# chart2.net
KiCad netlist of a schematic drawn in EAGLE
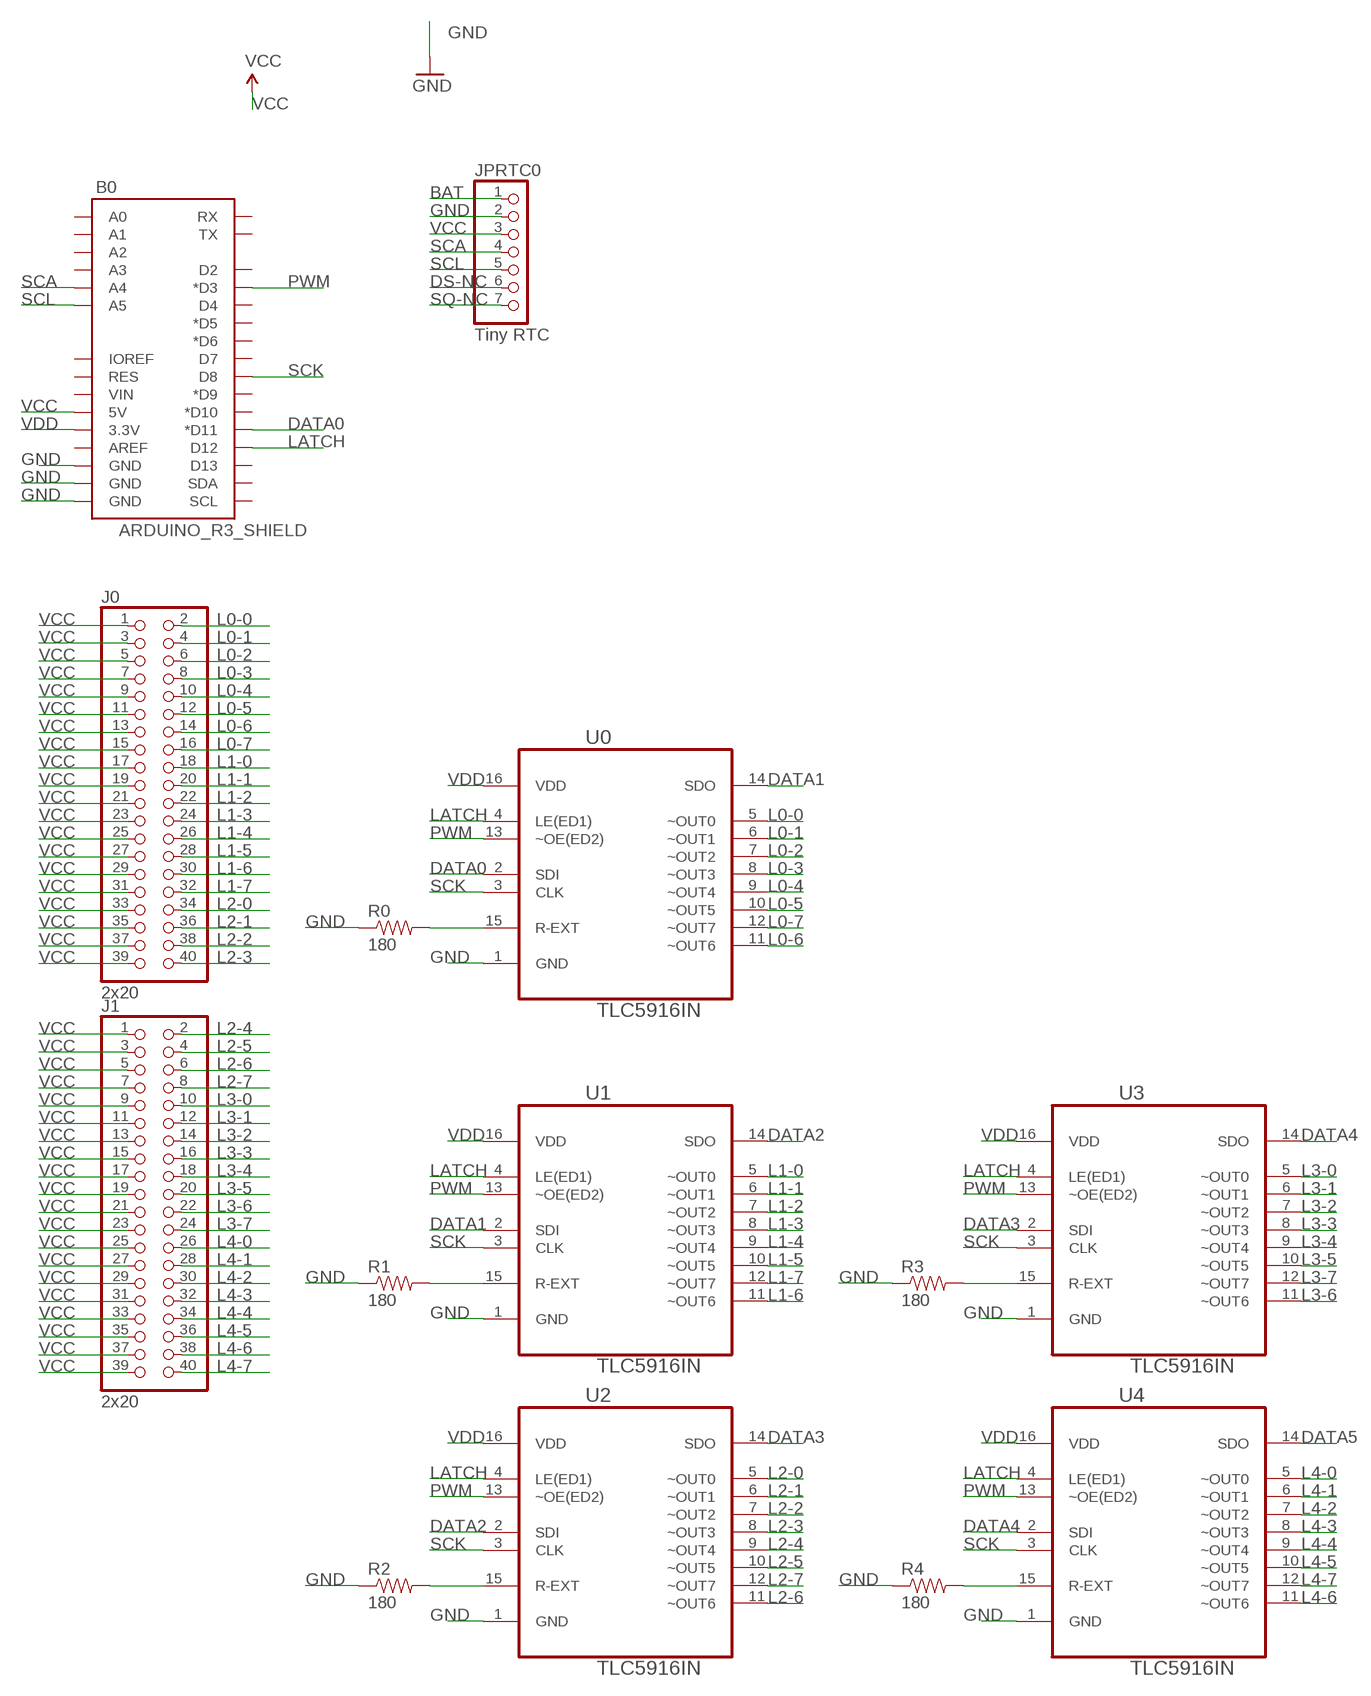
[diagram p0: schematic, sheet 1]

(export (version "E")
  (design (tool "Eeschema 10.0.6"))
  (components
    (comp (ref "B0")
      (value "ARDUINO_R3_SHIELD")
      (footprint "eagle-import:UNO_R3_SHIELD")
      (libsource (lib "eagle-import") (part "ARDUINO_R3_SHIELD"))
    )
    (comp (ref "J0")
      (value "2x20")
      (footprint "eagle-import:2X20_90")
      (libsource (lib "eagle-import") (part "PINHD-2X20/90"))
    )
    (comp (ref "J1")
      (value "2x20")
      (footprint "eagle-import:2X20_90")
      (libsource (lib "eagle-import") (part "PINHD-2X20/90"))
    )
    (comp (ref "JPRTC0")
      (value "Tiny RTC")
      (footprint "eagle-import:1X07")
      (libsource (lib "eagle-import") (part "PINHD-1X7"))
    )
    (comp (ref "R0")
      (value "180")
      (footprint "eagle-import:AXIAL-0.4")
      (libsource (lib "eagle-import") (part "RESISTORPTH-1/4W"))
    )
    (comp (ref "R1")
      (value "180")
      (footprint "eagle-import:AXIAL-0.4")
      (libsource (lib "eagle-import") (part "RESISTORPTH-1/4W"))
    )
    (comp (ref "R2")
      (value "180")
      (footprint "eagle-import:AXIAL-0.4")
      (libsource (lib "eagle-import") (part "RESISTORPTH-1/4W"))
    )
    (comp (ref "R3")
      (value "180")
      (footprint "eagle-import:AXIAL-0.4")
      (libsource (lib "eagle-import") (part "RESISTORPTH-1/4W"))
    )
    (comp (ref "R4")
      (value "180")
      (footprint "eagle-import:AXIAL-0.4")
      (libsource (lib "eagle-import") (part "RESISTORPTH-1/4W"))
    )
    (comp (ref "U0")
      (value "TLC5916IN")
      (footprint "eagle-import:DIP254P762X508-16")
      (libsource (lib "eagle-import") (part "TLC5916IN"))
    )
    (comp (ref "U1")
      (value "TLC5916IN")
      (footprint "eagle-import:DIP254P762X508-16")
      (libsource (lib "eagle-import") (part "TLC5916IN"))
    )
    (comp (ref "U2")
      (value "TLC5916IN")
      (footprint "eagle-import:DIP254P762X508-16")
      (libsource (lib "eagle-import") (part "TLC5916IN"))
    )
    (comp (ref "U3")
      (value "TLC5916IN")
      (footprint "eagle-import:DIP254P762X508-16")
      (libsource (lib "eagle-import") (part "TLC5916IN"))
    )
    (comp (ref "U4")
      (value "TLC5916IN")
      (footprint "eagle-import:DIP254P762X508-16")
      (libsource (lib "eagle-import") (part "TLC5916IN"))
    )
  )
  (nets
    (net (code "1") (name "/BAT") (class "Default")
      (node (ref "JPRTC0") (pin "1") (pinfunction "1_1") (pintype "passive"))
    )
    (net (code "2") (name "/DATA0") (class "Default")
      (node (ref "B0") (pin "D11") (pinfunction "*D11_D11") (pintype "bidirectional"))
      (node (ref "U0") (pin "2") (pinfunction "SDI_2") (pintype "input"))
    )
    (net (code "3") (name "/DATA1") (class "Default")
      (node (ref "U0") (pin "14") (pinfunction "SDO_14") (pintype "output"))
      (node (ref "U1") (pin "2") (pinfunction "SDI_2") (pintype "input"))
    )
    (net (code "4") (name "/DATA2") (class "Default")
      (node (ref "U1") (pin "14") (pinfunction "SDO_14") (pintype "output"))
      (node (ref "U2") (pin "2") (pinfunction "SDI_2") (pintype "input"))
    )
    (net (code "5") (name "/DATA3") (class "Default")
      (node (ref "U2") (pin "14") (pinfunction "SDO_14") (pintype "output"))
      (node (ref "U3") (pin "2") (pinfunction "SDI_2") (pintype "input"))
    )
    (net (code "6") (name "/DATA4") (class "Default")
      (node (ref "U3") (pin "14") (pinfunction "SDO_14") (pintype "output"))
      (node (ref "U4") (pin "2") (pinfunction "SDI_2") (pintype "input"))
    )
    (net (code "7") (name "/DATA5") (class "Default")
      (node (ref "U4") (pin "14") (pinfunction "SDO_14") (pintype "output"))
    )
    (net (code "8") (name "/DS-NC") (class "Default")
      (node (ref "JPRTC0") (pin "6") (pinfunction "6_6") (pintype "passive"))
    )
    (net (code "9") (name "/L0-0") (class "Default")
      (node (ref "J0") (pin "2") (pinfunction "2_2") (pintype "passive"))
      (node (ref "U0") (pin "5") (pinfunction "~{OUT0}_5") (pintype "output"))
    )
    (net (code "10") (name "/L0-1") (class "Default")
      (node (ref "J0") (pin "4") (pinfunction "4_4") (pintype "passive"))
      (node (ref "U0") (pin "6") (pinfunction "~{OUT1}_6") (pintype "output"))
    )
    (net (code "11") (name "/L0-2") (class "Default")
      (node (ref "J0") (pin "6") (pinfunction "6_6") (pintype "passive"))
      (node (ref "U0") (pin "7") (pinfunction "~{OUT2}_7") (pintype "output"))
    )
    (net (code "12") (name "/L0-3") (class "Default")
      (node (ref "J0") (pin "8") (pinfunction "8_8") (pintype "passive"))
      (node (ref "U0") (pin "8") (pinfunction "~{OUT3}_8") (pintype "output"))
    )
    (net (code "13") (name "/L0-4") (class "Default")
      (node (ref "J0") (pin "10") (pinfunction "10_10") (pintype "passive"))
      (node (ref "U0") (pin "9") (pinfunction "~{OUT4}_9") (pintype "output"))
    )
    (net (code "14") (name "/L0-5") (class "Default")
      (node (ref "J0") (pin "12") (pinfunction "12_12") (pintype "passive"))
      (node (ref "U0") (pin "10") (pinfunction "~{OUT5}_10") (pintype "output"))
    )
    (net (code "15") (name "/L0-6") (class "Default")
      (node (ref "J0") (pin "14") (pinfunction "14_14") (pintype "passive"))
      (node (ref "U0") (pin "11") (pinfunction "~{OUT6}_11") (pintype "output"))
    )
    (net (code "16") (name "/L0-7") (class "Default")
      (node (ref "J0") (pin "16") (pinfunction "16_16") (pintype "passive"))
      (node (ref "U0") (pin "12") (pinfunction "~{OUT7}_12") (pintype "output"))
    )
    (net (code "17") (name "/L1-0") (class "Default")
      (node (ref "J0") (pin "18") (pinfunction "18_18") (pintype "passive"))
      (node (ref "U1") (pin "5") (pinfunction "~{OUT0}_5") (pintype "output"))
    )
    (net (code "18") (name "/L1-1") (class "Default")
      (node (ref "J0") (pin "20") (pinfunction "20_20") (pintype "passive"))
      (node (ref "U1") (pin "6") (pinfunction "~{OUT1}_6") (pintype "output"))
    )
    (net (code "19") (name "/L1-2") (class "Default")
      (node (ref "J0") (pin "22") (pinfunction "22_22") (pintype "passive"))
      (node (ref "U1") (pin "7") (pinfunction "~{OUT2}_7") (pintype "output"))
    )
    (net (code "20") (name "/L1-3") (class "Default")
      (node (ref "J0") (pin "24") (pinfunction "24_24") (pintype "passive"))
      (node (ref "U1") (pin "8") (pinfunction "~{OUT3}_8") (pintype "output"))
    )
    (net (code "21") (name "/L1-4") (class "Default")
      (node (ref "J0") (pin "26") (pinfunction "26_26") (pintype "passive"))
      (node (ref "U1") (pin "9") (pinfunction "~{OUT4}_9") (pintype "output"))
    )
    (net (code "22") (name "/L1-5") (class "Default")
      (node (ref "J0") (pin "28") (pinfunction "28_28") (pintype "passive"))
      (node (ref "U1") (pin "10") (pinfunction "~{OUT5}_10") (pintype "output"))
    )
    (net (code "23") (name "/L1-6") (class "Default")
      (node (ref "J0") (pin "30") (pinfunction "30_30") (pintype "passive"))
      (node (ref "U1") (pin "11") (pinfunction "~{OUT6}_11") (pintype "output"))
    )
    (net (code "24") (name "/L1-7") (class "Default")
      (node (ref "J0") (pin "32") (pinfunction "32_32") (pintype "passive"))
      (node (ref "U1") (pin "12") (pinfunction "~{OUT7}_12") (pintype "output"))
    )
    (net (code "25") (name "/L2-0") (class "Default")
      (node (ref "J0") (pin "34") (pinfunction "34_34") (pintype "passive"))
      (node (ref "U2") (pin "5") (pinfunction "~{OUT0}_5") (pintype "output"))
    )
    (net (code "26") (name "/L2-1") (class "Default")
      (node (ref "J0") (pin "36") (pinfunction "36_36") (pintype "passive"))
      (node (ref "U2") (pin "6") (pinfunction "~{OUT1}_6") (pintype "output"))
    )
    (net (code "27") (name "/L2-2") (class "Default")
      (node (ref "J0") (pin "38") (pinfunction "38_38") (pintype "passive"))
      (node (ref "U2") (pin "7") (pinfunction "~{OUT2}_7") (pintype "output"))
    )
    (net (code "28") (name "/L2-3") (class "Default")
      (node (ref "J0") (pin "40") (pinfunction "40_40") (pintype "passive"))
      (node (ref "U2") (pin "8") (pinfunction "~{OUT3}_8") (pintype "output"))
    )
    (net (code "29") (name "/L2-4") (class "Default")
      (node (ref "J1") (pin "2") (pinfunction "2_2") (pintype "passive"))
      (node (ref "U2") (pin "9") (pinfunction "~{OUT4}_9") (pintype "output"))
    )
    (net (code "30") (name "/L2-5") (class "Default")
      (node (ref "J1") (pin "4") (pinfunction "4_4") (pintype "passive"))
      (node (ref "U2") (pin "10") (pinfunction "~{OUT5}_10") (pintype "output"))
    )
    (net (code "31") (name "/L2-6") (class "Default")
      (node (ref "J1") (pin "6") (pinfunction "6_6") (pintype "passive"))
      (node (ref "U2") (pin "11") (pinfunction "~{OUT6}_11") (pintype "output"))
    )
    (net (code "32") (name "/L2-7") (class "Default")
      (node (ref "J1") (pin "8") (pinfunction "8_8") (pintype "passive"))
      (node (ref "U2") (pin "12") (pinfunction "~{OUT7}_12") (pintype "output"))
    )
    (net (code "33") (name "/L3-0") (class "Default")
      (node (ref "J1") (pin "10") (pinfunction "10_10") (pintype "passive"))
      (node (ref "U3") (pin "5") (pinfunction "~{OUT0}_5") (pintype "output"))
    )
    (net (code "34") (name "/L3-1") (class "Default")
      (node (ref "J1") (pin "12") (pinfunction "12_12") (pintype "passive"))
      (node (ref "U3") (pin "6") (pinfunction "~{OUT1}_6") (pintype "output"))
    )
    (net (code "35") (name "/L3-2") (class "Default")
      (node (ref "J1") (pin "14") (pinfunction "14_14") (pintype "passive"))
      (node (ref "U3") (pin "7") (pinfunction "~{OUT2}_7") (pintype "output"))
    )
    (net (code "36") (name "/L3-3") (class "Default")
      (node (ref "J1") (pin "16") (pinfunction "16_16") (pintype "passive"))
      (node (ref "U3") (pin "8") (pinfunction "~{OUT3}_8") (pintype "output"))
    )
    (net (code "37") (name "/L3-4") (class "Default")
      (node (ref "J1") (pin "18") (pinfunction "18_18") (pintype "passive"))
      (node (ref "U3") (pin "9") (pinfunction "~{OUT4}_9") (pintype "output"))
    )
    (net (code "38") (name "/L3-5") (class "Default")
      (node (ref "J1") (pin "20") (pinfunction "20_20") (pintype "passive"))
      (node (ref "U3") (pin "10") (pinfunction "~{OUT5}_10") (pintype "output"))
    )
    (net (code "39") (name "/L3-6") (class "Default")
      (node (ref "J1") (pin "22") (pinfunction "22_22") (pintype "passive"))
      (node (ref "U3") (pin "11") (pinfunction "~{OUT6}_11") (pintype "output"))
    )
    (net (code "40") (name "/L3-7") (class "Default")
      (node (ref "J1") (pin "24") (pinfunction "24_24") (pintype "passive"))
      (node (ref "U3") (pin "12") (pinfunction "~{OUT7}_12") (pintype "output"))
    )
    (net (code "41") (name "/L4-0") (class "Default")
      (node (ref "J1") (pin "26") (pinfunction "26_26") (pintype "passive"))
      (node (ref "U4") (pin "5") (pinfunction "~{OUT0}_5") (pintype "output"))
    )
    (net (code "42") (name "/L4-1") (class "Default")
      (node (ref "J1") (pin "28") (pinfunction "28_28") (pintype "passive"))
      (node (ref "U4") (pin "6") (pinfunction "~{OUT1}_6") (pintype "output"))
    )
    (net (code "43") (name "/L4-2") (class "Default")
      (node (ref "J1") (pin "30") (pinfunction "30_30") (pintype "passive"))
      (node (ref "U4") (pin "7") (pinfunction "~{OUT2}_7") (pintype "output"))
    )
    (net (code "44") (name "/L4-3") (class "Default")
      (node (ref "J1") (pin "32") (pinfunction "32_32") (pintype "passive"))
      (node (ref "U4") (pin "8") (pinfunction "~{OUT3}_8") (pintype "output"))
    )
    (net (code "45") (name "/L4-4") (class "Default")
      (node (ref "J1") (pin "34") (pinfunction "34_34") (pintype "passive"))
      (node (ref "U4") (pin "9") (pinfunction "~{OUT4}_9") (pintype "output"))
    )
    (net (code "46") (name "/L4-5") (class "Default")
      (node (ref "J1") (pin "36") (pinfunction "36_36") (pintype "passive"))
      (node (ref "U4") (pin "10") (pinfunction "~{OUT5}_10") (pintype "output"))
    )
    (net (code "47") (name "/L4-6") (class "Default")
      (node (ref "J1") (pin "38") (pinfunction "38_38") (pintype "passive"))
      (node (ref "U4") (pin "11") (pinfunction "~{OUT6}_11") (pintype "output"))
    )
    (net (code "48") (name "/L4-7") (class "Default")
      (node (ref "J1") (pin "40") (pinfunction "40_40") (pintype "passive"))
      (node (ref "U4") (pin "12") (pinfunction "~{OUT7}_12") (pintype "output"))
    )
    (net (code "49") (name "/LATCH") (class "Default")
      (node (ref "B0") (pin "D12") (pinfunction "D12_D12") (pintype "bidirectional"))
      (node (ref "U0") (pin "4") (pinfunction "LE(ED1)_4") (pintype "input"))
      (node (ref "U1") (pin "4") (pinfunction "LE(ED1)_4") (pintype "input"))
      (node (ref "U2") (pin "4") (pinfunction "LE(ED1)_4") (pintype "input"))
      (node (ref "U3") (pin "4") (pinfunction "LE(ED1)_4") (pintype "input"))
      (node (ref "U4") (pin "4") (pinfunction "LE(ED1)_4") (pintype "input"))
    )
    (net (code "50") (name "/PWM") (class "Default")
      (node (ref "B0") (pin "D3") (pinfunction "*D3_D3") (pintype "bidirectional"))
      (node (ref "U0") (pin "13") (pinfunction "~{OE(ED2})_13") (pintype "input"))
      (node (ref "U1") (pin "13") (pinfunction "~{OE(ED2})_13") (pintype "input"))
      (node (ref "U2") (pin "13") (pinfunction "~{OE(ED2})_13") (pintype "input"))
      (node (ref "U3") (pin "13") (pinfunction "~{OE(ED2})_13") (pintype "input"))
      (node (ref "U4") (pin "13") (pinfunction "~{OE(ED2})_13") (pintype "input"))
    )
    (net (code "51") (name "/SCA") (class "Default")
      (node (ref "B0") (pin "A4") (pinfunction "A4_A4") (pintype "bidirectional"))
      (node (ref "JPRTC0") (pin "4") (pinfunction "4_4") (pintype "passive"))
    )
    (net (code "52") (name "/SCK") (class "Default")
      (node (ref "B0") (pin "D8") (pinfunction "D8_D8") (pintype "bidirectional"))
      (node (ref "U0") (pin "3") (pinfunction "CLK_3") (pintype "input"))
      (node (ref "U1") (pin "3") (pinfunction "CLK_3") (pintype "input"))
      (node (ref "U2") (pin "3") (pinfunction "CLK_3") (pintype "input"))
      (node (ref "U3") (pin "3") (pinfunction "CLK_3") (pintype "input"))
      (node (ref "U4") (pin "3") (pinfunction "CLK_3") (pintype "input"))
    )
    (net (code "53") (name "/SCL") (class "Default")
      (node (ref "B0") (pin "A5") (pinfunction "A5_A5") (pintype "bidirectional"))
      (node (ref "JPRTC0") (pin "5") (pinfunction "5_5") (pintype "passive"))
    )
    (net (code "54") (name "/SQ-NC") (class "Default")
      (node (ref "JPRTC0") (pin "7") (pinfunction "7_7") (pintype "passive"))
    )
    (net (code "55") (name "/VDD") (class "Default")
      (node (ref "B0") (pin "3.3V") (pinfunction "3.3V_3.3V") (pintype "bidirectional"))
      (node (ref "U0") (pin "16") (pinfunction "VDD_16") (pintype "power_in"))
      (node (ref "U1") (pin "16") (pinfunction "VDD_16") (pintype "power_in"))
      (node (ref "U2") (pin "16") (pinfunction "VDD_16") (pintype "power_in"))
      (node (ref "U3") (pin "16") (pinfunction "VDD_16") (pintype "power_in"))
      (node (ref "U4") (pin "16") (pinfunction "VDD_16") (pintype "power_in"))
    )
    (net (code "56") (name "GND") (class "Default")
      (node (ref "B0") (pin "GND@0") (pinfunction "GND_GND@0") (pintype "bidirectional"))
      (node (ref "B0") (pin "GND@1") (pinfunction "GND_GND@1") (pintype "bidirectional"))
      (node (ref "B0") (pin "GND@2") (pinfunction "GND_GND@2") (pintype "bidirectional"))
      (node (ref "JPRTC0") (pin "2") (pinfunction "2_2") (pintype "passive"))
      (node (ref "R0") (pin "P$1") (pinfunction "1_P$1") (pintype "passive"))
      (node (ref "R1") (pin "P$1") (pinfunction "1_P$1") (pintype "passive"))
      (node (ref "R2") (pin "P$1") (pinfunction "1_P$1") (pintype "passive"))
      (node (ref "R3") (pin "P$1") (pinfunction "1_P$1") (pintype "passive"))
      (node (ref "R4") (pin "P$1") (pinfunction "1_P$1") (pintype "passive"))
      (node (ref "U0") (pin "1") (pinfunction "GND_1") (pintype "passive"))
      (node (ref "U1") (pin "1") (pinfunction "GND_1") (pintype "passive"))
      (node (ref "U2") (pin "1") (pinfunction "GND_1") (pintype "passive"))
      (node (ref "U3") (pin "1") (pinfunction "GND_1") (pintype "passive"))
      (node (ref "U4") (pin "1") (pinfunction "GND_1") (pintype "passive"))
    )
    (net (code "57") (name "Net-(R0-2)") (class "Default")
      (node (ref "R0") (pin "P$2") (pinfunction "2_P$2") (pintype "passive"))
      (node (ref "U0") (pin "15") (pinfunction "R-EXT_15") (pintype "passive"))
    )
    (net (code "58") (name "Net-(R1-2)") (class "Default")
      (node (ref "R1") (pin "P$2") (pinfunction "2_P$2") (pintype "passive"))
      (node (ref "U1") (pin "15") (pinfunction "R-EXT_15") (pintype "passive"))
    )
    (net (code "59") (name "Net-(R2-2)") (class "Default")
      (node (ref "R2") (pin "P$2") (pinfunction "2_P$2") (pintype "passive"))
      (node (ref "U2") (pin "15") (pinfunction "R-EXT_15") (pintype "passive"))
    )
    (net (code "60") (name "Net-(R3-2)") (class "Default")
      (node (ref "R3") (pin "P$2") (pinfunction "2_P$2") (pintype "passive"))
      (node (ref "U3") (pin "15") (pinfunction "R-EXT_15") (pintype "passive"))
    )
    (net (code "61") (name "Net-(R4-2)") (class "Default")
      (node (ref "R4") (pin "P$2") (pinfunction "2_P$2") (pintype "passive"))
      (node (ref "U4") (pin "15") (pinfunction "R-EXT_15") (pintype "passive"))
    )
    (net (code "62") (name "VCC") (class "Default")
      (node (ref "B0") (pin "5V") (pinfunction "5V_5V") (pintype "bidirectional"))
      (node (ref "J0") (pin "1") (pinfunction "1_1") (pintype "passive"))
      (node (ref "J0") (pin "11") (pinfunction "11_11") (pintype "passive"))
      (node (ref "J0") (pin "13") (pinfunction "13_13") (pintype "passive"))
      (node (ref "J0") (pin "15") (pinfunction "15_15") (pintype "passive"))
      (node (ref "J0") (pin "17") (pinfunction "17_17") (pintype "passive"))
      (node (ref "J0") (pin "19") (pinfunction "19_19") (pintype "passive"))
      (node (ref "J0") (pin "21") (pinfunction "21_21") (pintype "passive"))
      (node (ref "J0") (pin "23") (pinfunction "23_23") (pintype "passive"))
      (node (ref "J0") (pin "25") (pinfunction "25_25") (pintype "passive"))
      (node (ref "J0") (pin "27") (pinfunction "27_27") (pintype "passive"))
      (node (ref "J0") (pin "29") (pinfunction "29_29") (pintype "passive"))
      (node (ref "J0") (pin "3") (pinfunction "3_3") (pintype "passive"))
      (node (ref "J0") (pin "31") (pinfunction "31_31") (pintype "passive"))
      (node (ref "J0") (pin "33") (pinfunction "33_33") (pintype "passive"))
      (node (ref "J0") (pin "35") (pinfunction "35_35") (pintype "passive"))
      (node (ref "J0") (pin "37") (pinfunction "37_37") (pintype "passive"))
      (node (ref "J0") (pin "39") (pinfunction "39_39") (pintype "passive"))
      (node (ref "J0") (pin "5") (pinfunction "5_5") (pintype "passive"))
      (node (ref "J0") (pin "7") (pinfunction "7_7") (pintype "passive"))
      (node (ref "J0") (pin "9") (pinfunction "9_9") (pintype "passive"))
      (node (ref "J1") (pin "1") (pinfunction "1_1") (pintype "passive"))
      (node (ref "J1") (pin "11") (pinfunction "11_11") (pintype "passive"))
      (node (ref "J1") (pin "13") (pinfunction "13_13") (pintype "passive"))
      (node (ref "J1") (pin "15") (pinfunction "15_15") (pintype "passive"))
      (node (ref "J1") (pin "17") (pinfunction "17_17") (pintype "passive"))
      (node (ref "J1") (pin "19") (pinfunction "19_19") (pintype "passive"))
      (node (ref "J1") (pin "21") (pinfunction "21_21") (pintype "passive"))
      (node (ref "J1") (pin "23") (pinfunction "23_23") (pintype "passive"))
      (node (ref "J1") (pin "25") (pinfunction "25_25") (pintype "passive"))
      (node (ref "J1") (pin "27") (pinfunction "27_27") (pintype "passive"))
      (node (ref "J1") (pin "29") (pinfunction "29_29") (pintype "passive"))
      (node (ref "J1") (pin "3") (pinfunction "3_3") (pintype "passive"))
      (node (ref "J1") (pin "31") (pinfunction "31_31") (pintype "passive"))
      (node (ref "J1") (pin "33") (pinfunction "33_33") (pintype "passive"))
      (node (ref "J1") (pin "35") (pinfunction "35_35") (pintype "passive"))
      (node (ref "J1") (pin "37") (pinfunction "37_37") (pintype "passive"))
      (node (ref "J1") (pin "39") (pinfunction "39_39") (pintype "passive"))
      (node (ref "J1") (pin "5") (pinfunction "5_5") (pintype "passive"))
      (node (ref "J1") (pin "7") (pinfunction "7_7") (pintype "passive"))
      (node (ref "J1") (pin "9") (pinfunction "9_9") (pintype "passive"))
      (node (ref "JPRTC0") (pin "3") (pinfunction "3_3") (pintype "passive"))
    )
    (net (code "63") (name "unconnected-(B0-*D5-PadD5)") (class "Default")
      (node (ref "B0") (pin "D5") (pinfunction "*D5_D5") (pintype "bidirectional"))
    )
    (net (code "64") (name "unconnected-(B0-*D6-PadD6)") (class "Default")
      (node (ref "B0") (pin "D6") (pinfunction "*D6_D6") (pintype "bidirectional"))
    )
    (net (code "65") (name "unconnected-(B0-*D9-PadD9)") (class "Default")
      (node (ref "B0") (pin "D9") (pinfunction "*D9_D9") (pintype "bidirectional"))
    )
    (net (code "66") (name "unconnected-(B0-*D10-PadD10)") (class "Default")
      (node (ref "B0") (pin "D10") (pinfunction "*D10_D10") (pintype "bidirectional"))
    )
    (net (code "67") (name "unconnected-(B0-PadA0)") (class "Default")
      (node (ref "B0") (pin "A0") (pinfunction "A0_A0") (pintype "bidirectional"))
    )
    (net (code "68") (name "unconnected-(B0-PadA1)") (class "Default")
      (node (ref "B0") (pin "A1") (pinfunction "A1_A1") (pintype "bidirectional"))
    )
    (net (code "69") (name "unconnected-(B0-PadA2)") (class "Default")
      (node (ref "B0") (pin "A2") (pinfunction "A2_A2") (pintype "bidirectional"))
    )
    (net (code "70") (name "unconnected-(B0-PadA3)") (class "Default")
      (node (ref "B0") (pin "A3") (pinfunction "A3_A3") (pintype "bidirectional"))
    )
    (net (code "71") (name "unconnected-(B0-PadAREF)") (class "Default")
      (node (ref "B0") (pin "AREF") (pinfunction "AREF_AREF") (pintype "bidirectional"))
    )
    (net (code "72") (name "unconnected-(B0-PadD2)") (class "Default")
      (node (ref "B0") (pin "D2") (pinfunction "D2_D2") (pintype "bidirectional"))
    )
    (net (code "73") (name "unconnected-(B0-PadD4)") (class "Default")
      (node (ref "B0") (pin "D4") (pinfunction "D4_D4") (pintype "bidirectional"))
    )
    (net (code "74") (name "unconnected-(B0-PadD7)") (class "Default")
      (node (ref "B0") (pin "D7") (pinfunction "D7_D7") (pintype "bidirectional"))
    )
    (net (code "75") (name "unconnected-(B0-PadD13)") (class "Default")
      (node (ref "B0") (pin "D13") (pinfunction "D13_D13") (pintype "bidirectional"))
    )
    (net (code "76") (name "unconnected-(B0-PadIOREF)") (class "Default")
      (node (ref "B0") (pin "IOREF") (pinfunction "IOREF_IOREF") (pintype "bidirectional"))
    )
    (net (code "77") (name "unconnected-(B0-PadRES)") (class "Default")
      (node (ref "B0") (pin "RES") (pinfunction "RES_RES") (pintype "bidirectional"))
    )
    (net (code "78") (name "unconnected-(B0-PadRX)") (class "Default")
      (node (ref "B0") (pin "RX") (pinfunction "RX_RX") (pintype "bidirectional"))
    )
    (net (code "79") (name "unconnected-(B0-PadSCL)") (class "Default")
      (node (ref "B0") (pin "SCL") (pinfunction "SCL_SCL") (pintype "bidirectional"))
    )
    (net (code "80") (name "unconnected-(B0-PadSDA)") (class "Default")
      (node (ref "B0") (pin "SDA") (pinfunction "SDA_SDA") (pintype "bidirectional"))
    )
    (net (code "81") (name "unconnected-(B0-PadTX)") (class "Default")
      (node (ref "B0") (pin "TX") (pinfunction "TX_TX") (pintype "bidirectional"))
    )
    (net (code "82") (name "unconnected-(B0-PadVIN)") (class "Default")
      (node (ref "B0") (pin "VIN") (pinfunction "VIN_VIN") (pintype "bidirectional"))
    )
  )
)
